# H-00488_-_Power.net
KiCad netlist of a schematic drawn in Altium Designer
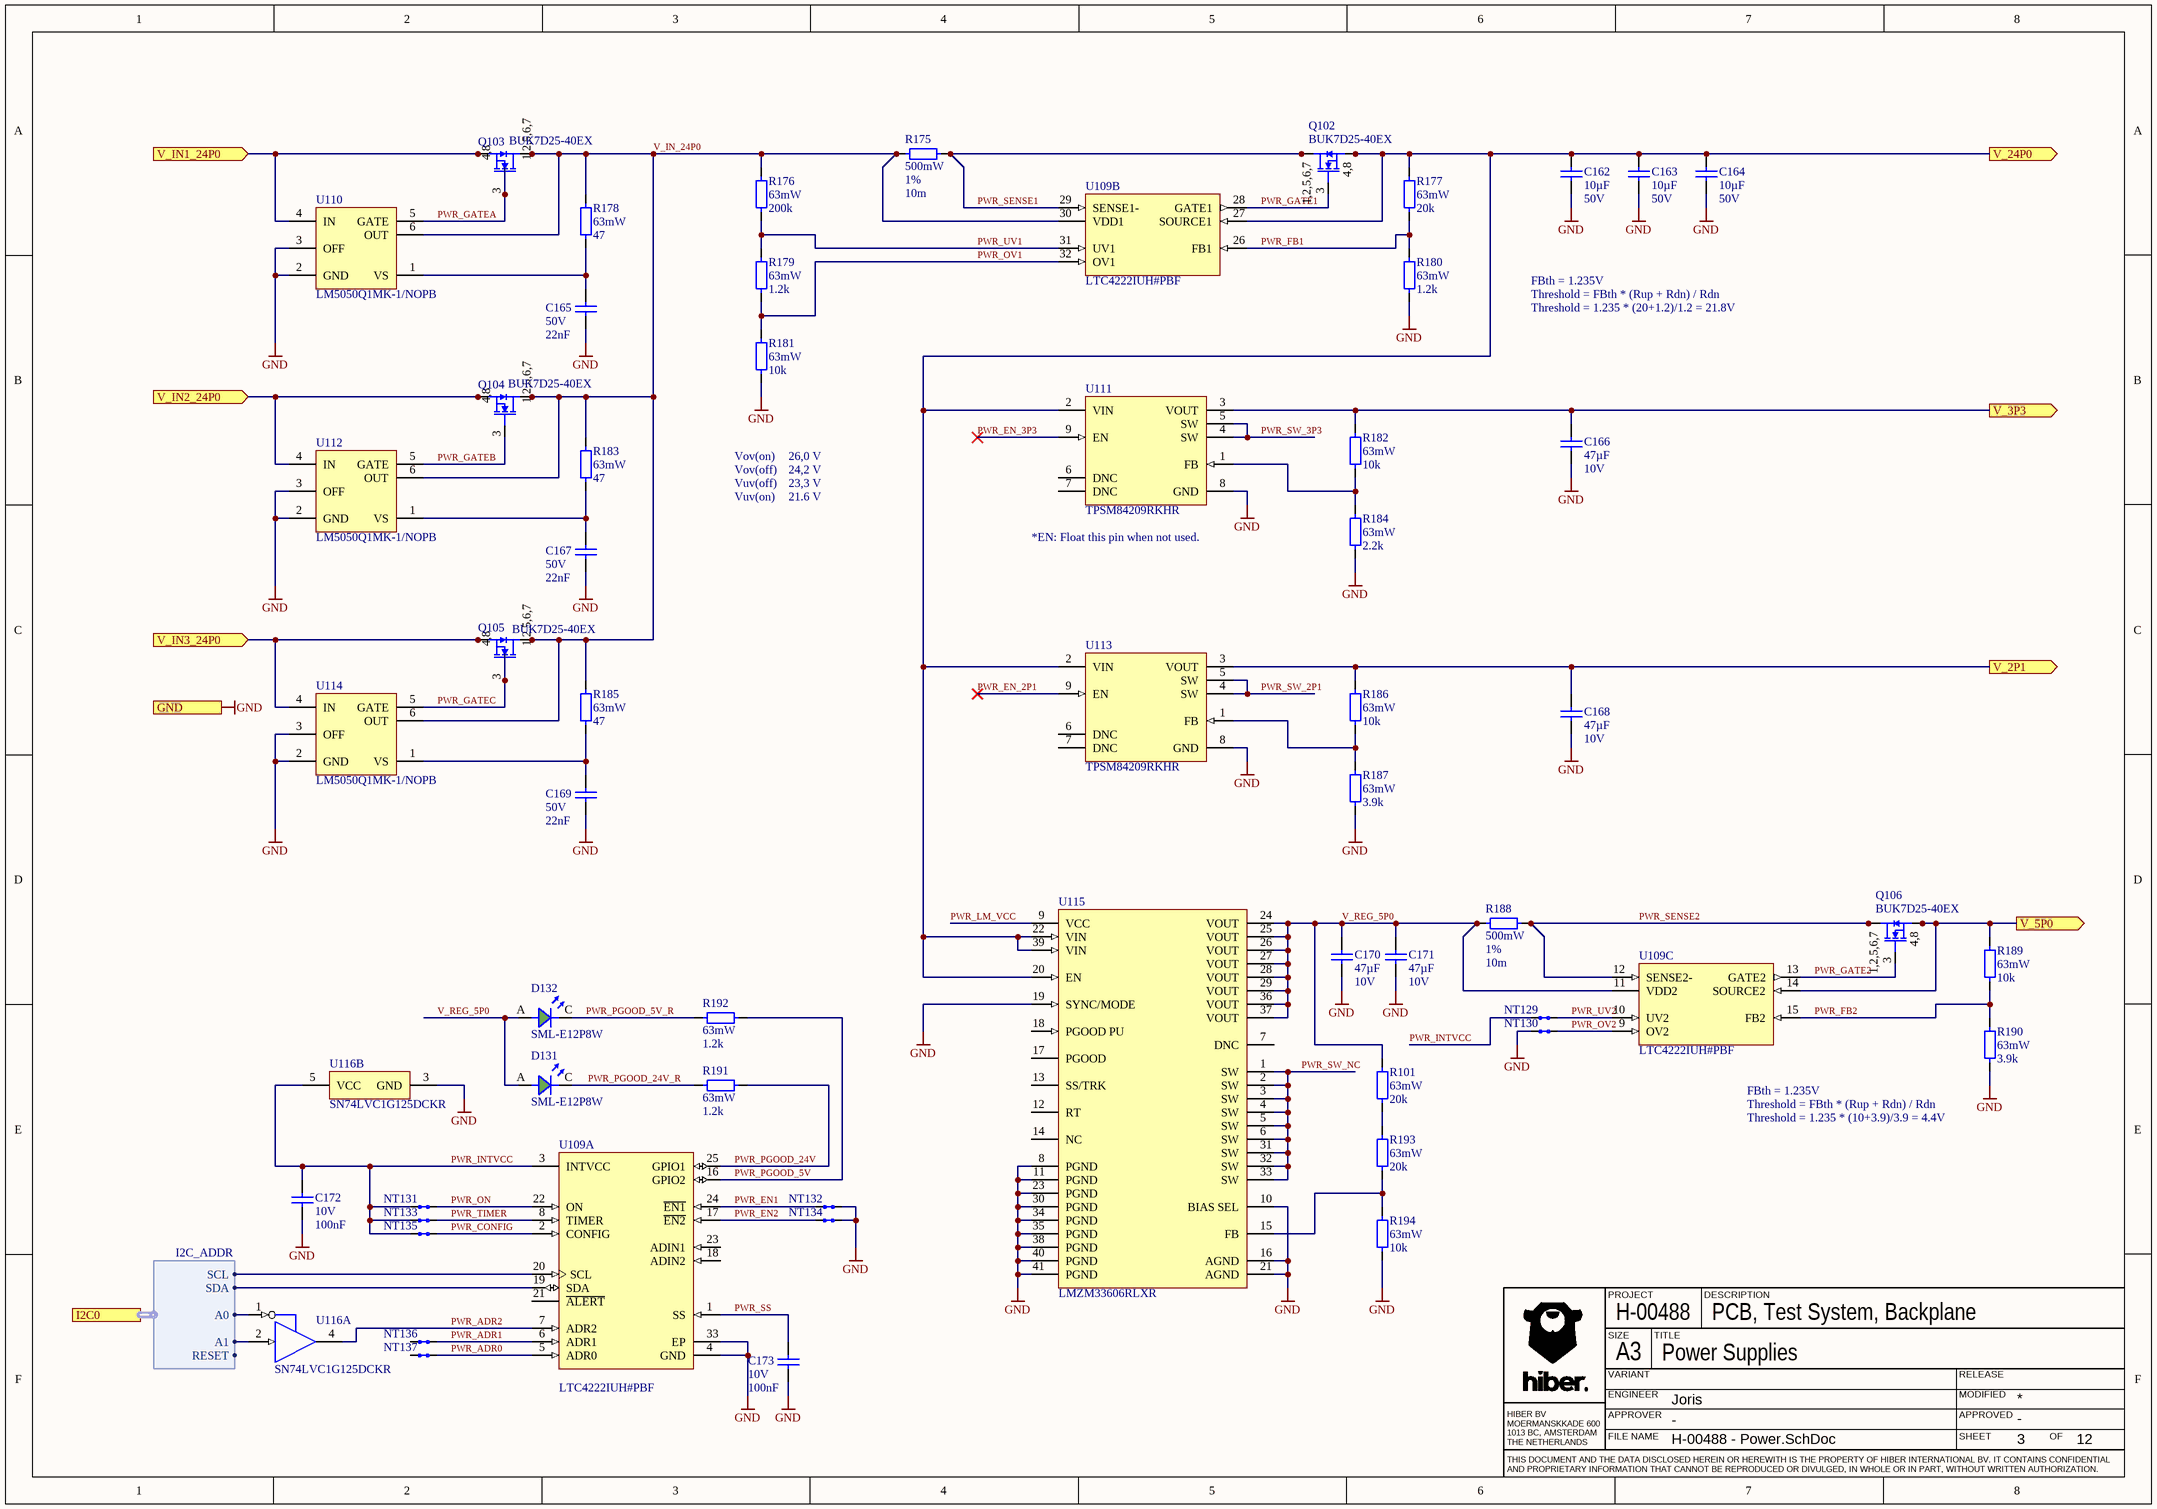
[diagram p0: H-00488 - Power.SchDoc]

(export (version "E")
  (design (tool "Eeschema 10.0.6"))
  (components
    (comp (ref "C162")
      (value "10µF")
      (footprint "CAPC320X250X245L50N")
      (description "CAP Standard 1210 (3225) 10,0uF 50V X7R (Standard)")
      (fields
        (field (name "TOLERANCE") "10%")
        (field (name "RATED VOLTAGE") "50V")
        (field (name "Comment") "C1210C106K5RACTU")
      )
      (libsource (lib "Hiber") (part "CAPACITOR"))
    )
    (comp (ref "C163")
      (value "10µF")
      (footprint "CAPC320X250X245L50N")
      (description "CAP Standard 1210 (3225) 10,0uF 50V X7R (Standard)")
      (fields
        (field (name "TOLERANCE") "10%")
        (field (name "RATED VOLTAGE") "50V")
        (field (name "Comment") "C1210C106K5RACTU")
      )
      (libsource (lib "Hiber") (part "CAPACITOR"))
    )
    (comp (ref "C164")
      (value "10µF")
      (footprint "CAPC320X250X245L50N")
      (description "CAP Standard 1210 (3225) 10,0uF 50V X7R (Standard)")
      (fields
        (field (name "TOLERANCE") "10%")
        (field (name "RATED VOLTAGE") "50V")
        (field (name "Comment") "C1210C106K5RACTU")
      )
      (libsource (lib "Hiber") (part "CAPACITOR"))
    )
    (comp (ref "C165")
      (value "22nF")
      (footprint "CAPC100X50X55L30N")
      (description "CAP Standard 0402 (1005) 22,0nF 50V X7R (Standard)")
      (fields
        (field (name "RATED VOLTAGE") "50V")
        (field (name "TOLERANCE") "10%")
        (field (name "Comment") "C0402C223K5RACTU")
      )
      (libsource (lib "Hiber") (part "CAPACITOR"))
    )
    (comp (ref "C166")
      (value "47µF")
      (footprint "CAPC320X250X170L50N")
      (description "CAP Standard 1210 (3225) 47,0uF 10V X7R (Standard)")
      (fields
        (field (name "RATED VOLTAGE") "10V")
        (field (name "TOLERANCE") "20%")
        (field (name "Comment") "C1210C476M8RACTU")
      )
      (libsource (lib "Hiber") (part "CAPACITOR"))
    )
    (comp (ref "C167")
      (value "22nF")
      (footprint "CAPC100X50X55L30N")
      (description "CAP Standard 0402 (1005) 22,0nF 50V X7R (Standard)")
      (fields
        (field (name "RATED VOLTAGE") "50V")
        (field (name "TOLERANCE") "10%")
        (field (name "Comment") "C0402C223K5RACTU")
      )
      (libsource (lib "Hiber") (part "CAPACITOR"))
    )
    (comp (ref "C168")
      (value "47µF")
      (footprint "CAPC320X250X170L50N")
      (description "CAP Standard 1210 (3225) 47,0uF 10V X7R (Standard)")
      (fields
        (field (name "RATED VOLTAGE") "10V")
        (field (name "TOLERANCE") "20%")
        (field (name "Comment") "C1210C476M8RACTU")
      )
      (libsource (lib "Hiber") (part "CAPACITOR"))
    )
    (comp (ref "C169")
      (value "22nF")
      (footprint "CAPC100X50X55L30N")
      (description "CAP Standard 0402 (1005) 22,0nF 50V X7R (Standard)")
      (fields
        (field (name "RATED VOLTAGE") "50V")
        (field (name "TOLERANCE") "10%")
        (field (name "Comment") "C0402C223K5RACTU")
      )
      (libsource (lib "Hiber") (part "CAPACITOR"))
    )
    (comp (ref "C170")
      (value "47µF")
      (footprint "CAPC320X250X170L50N")
      (description "CAP Standard 1210 (3225) 47,0uF 10V X7R (Standard)")
      (fields
        (field (name "RATED VOLTAGE") "10V")
        (field (name "TOLERANCE") "20%")
        (field (name "Comment") "C1210C476M8RACTU")
      )
      (libsource (lib "Hiber") (part "CAPACITOR"))
    )
    (comp (ref "C171")
      (value "47µF")
      (footprint "CAPC320X250X170L50N")
      (description "CAP Standard 1210 (3225) 47,0uF 10V X7R (Standard)")
      (fields
        (field (name "RATED VOLTAGE") "10V")
        (field (name "TOLERANCE") "20%")
        (field (name "Comment") "C1210C476M8RACTU")
      )
      (libsource (lib "Hiber") (part "CAPACITOR"))
    )
    (comp (ref "C172")
      (value "100nF")
      (footprint "CAPC100X50X55L30N")
      (description "CAP Standard 0402 (1005) 100,0nF 10V X7R (Standard)")
      (fields
        (field (name "RATED VOLTAGE") "10V")
        (field (name "TOLERANCE") "10%")
        (field (name "Comment") "C0402C104K8RACTU")
      )
      (libsource (lib "Hiber Vault") (part "CAPACITOR"))
    )
    (comp (ref "C173")
      (value "100nF")
      (footprint "CAPC100X50X55L30N")
      (description "CAP Standard 0402 (1005) 100,0nF 10V X7R (Standard)")
      (fields
        (field (name "RATED VOLTAGE") "10V")
        (field (name "TOLERANCE") "10%")
        (field (name "Comment") "C0402C104K8RACTU")
      )
      (libsource (lib "Hiber Vault") (part "CAPACITOR"))
    )
    (comp (ref "D131")
      (value "SML-E12P8W")
      (footprint "LEDC170X80X80L20_GREEN")
      (description "LED Green Diffused 0603 SMD")
      (libsource (lib "Hiber") (part "DIODE-LED-GREEN"))
    )
    (comp (ref "D132")
      (value "SML-E12P8W")
      (footprint "LEDC170X80X80L20_GREEN")
      (description "LED Green Diffused 0603 SMD")
      (libsource (lib "Hiber") (part "DIODE-LED-GREEN"))
    )
    (comp (ref "NT129")
      (value "NET-TIE")
      (footprint "NT200")
      (description "Net Tie, Inline")
      (libsource (lib "Hiber") (part "NET-TIE"))
    )
    (comp (ref "NT130")
      (value "NET-TIE")
      (footprint "NT200")
      (description "Net Tie, Inline")
      (libsource (lib "Hiber") (part "NET-TIE"))
    )
    (comp (ref "NT131")
      (value "NET-TIE")
      (footprint "NT200")
      (description "Net Tie, Inline")
      (libsource (lib "Hiber") (part "NET-TIE"))
    )
    (comp (ref "NT132")
      (value "NET-TIE")
      (footprint "NT200")
      (description "Net Tie, Inline")
      (libsource (lib "Hiber") (part "NET-TIE"))
    )
    (comp (ref "NT133")
      (value "NET-TIE")
      (footprint "NT200")
      (description "Net Tie, Inline")
      (libsource (lib "Hiber") (part "NET-TIE"))
    )
    (comp (ref "NT134")
      (value "NET-TIE")
      (footprint "NT200")
      (description "Net Tie, Inline")
      (libsource (lib "Hiber") (part "NET-TIE"))
    )
    (comp (ref "NT135")
      (value "NET-TIE")
      (footprint "NT200")
      (description "Net Tie, Inline")
      (libsource (lib "Hiber") (part "NET-TIE"))
    )
    (comp (ref "NT136")
      (value "NET-TIE")
      (footprint "NT200")
      (description "Net Tie, Inline")
      (libsource (lib "Hiber") (part "NET-TIE"))
    )
    (comp (ref "NT137")
      (value "NET-TIE")
      (footprint "NT200")
      (description "Net Tie, Inline")
      (libsource (lib "Hiber") (part "NET-TIE"))
    )
    (comp (ref "Q102")
      (value "BUK7D25-40EX")
      (footprint "NEXPERIA_SOT1220")
      (description "BUK7D25 Series 40V Surface-Mounted N-channel Trench MOSFET - SOT1118")
      (libsource (lib "Hiber") (part "MOSFET-N-8P-SOT1220"))
    )
    (comp (ref "Q103")
      (value "BUK7D25-40EX")
      (footprint "NEXPERIA_SOT1220")
      (description "BUK7D25 Series 40V Surface-Mounted N-channel Trench MOSFET - SOT1118")
      (libsource (lib "Hiber") (part "MOSFET-N-8P-SOT1220"))
    )
    (comp (ref "Q104")
      (value "BUK7D25-40EX")
      (footprint "NEXPERIA_SOT1220")
      (description "BUK7D25 Series 40V Surface-Mounted N-channel Trench MOSFET - SOT1118")
      (libsource (lib "Hiber") (part "MOSFET-N-8P-SOT1220"))
    )
    (comp (ref "Q105")
      (value "BUK7D25-40EX")
      (footprint "NEXPERIA_SOT1220")
      (description "BUK7D25 Series 40V Surface-Mounted N-channel Trench MOSFET - SOT1118")
      (libsource (lib "Hiber") (part "MOSFET-N-8P-SOT1220"))
    )
    (comp (ref "Q106")
      (value "BUK7D25-40EX")
      (footprint "NEXPERIA_SOT1220")
      (description "BUK7D25 Series 40V Surface-Mounted N-channel Trench MOSFET - SOT1118")
      (libsource (lib "Hiber") (part "MOSFET-N-8P-SOT1220"))
    )
    (comp (ref "R101")
      (value "20k")
      (footprint "RESC100X50X40L25N")
      (description "RES Standard Thick Film 0402 20K0 ±1% 0,063W")
      (fields
        (field (name "RATED POWER") "63mW")
        (field (name "TOLERANCE") "1%")
        (field (name "Comment") "CRCW040220K0FKED")
      )
      (libsource (lib "Hiber") (part "RESISTOR-2P"))
    )
    (comp (ref "R175")
      (value "10m")
      (footprint "RESC200X125X70L40M")
      (description "RES Power Metal Strip 0805 0R01 ±1% 0,5W")
      (fields
        (field (name "RATED POWER") "500mW")
        (field (name "TOLERANCE") "1%")
        (field (name "Comment") "WSLP0805R0100FEA")
      )
      (libsource (lib "Hiber Vault") (part "RESISTOR-2P"))
    )
    (comp (ref "R176")
      (value "200k")
      (footprint "RESC100X50X40L25N")
      (description "RES Standard Thick Film 0402 200K ±1% 0,063W")
      (fields
        (field (name "RATED POWER") "63mW")
        (field (name "TOLERANCE") "1%")
        (field (name "Comment") "CRCW0402200KFKED")
      )
      (libsource (lib "Hiber") (part "RESISTOR-2P"))
    )
    (comp (ref "R177")
      (value "20k")
      (footprint "RESC100X50X40L25N")
      (description "RES Standard Thick Film 0402 20K0 ±1% 0,063W")
      (fields
        (field (name "RATED POWER") "63mW")
        (field (name "TOLERANCE") "1%")
        (field (name "Comment") "CRCW040220K0FKED")
      )
      (libsource (lib "Hiber") (part "RESISTOR-2P"))
    )
    (comp (ref "R178")
      (value "47")
      (footprint "RESC100X50X40L25N")
      (description "RES Standard Thick Film 0402 47R0 ±1% 0,063W")
      (fields
        (field (name "RATED POWER") "63mW")
        (field (name "TOLERANCE") "1%")
        (field (name "Comment") "CRCW040247R0FKED")
      )
      (libsource (lib "Hiber") (part "RESISTOR-2P"))
    )
    (comp (ref "R179")
      (value "1.2k")
      (footprint "RESC100X50X40L25N")
      (description "RES Standard Thick Film 0402 1K20 ±1% 0,063W")
      (fields
        (field (name "RATED POWER") "63mW")
        (field (name "TOLERANCE") "1%")
        (field (name "Comment") "CRCW04021K20FKED")
      )
      (libsource (lib "Hiber") (part "RESISTOR-2P"))
    )
    (comp (ref "R180")
      (value "1.2k")
      (footprint "RESC100X50X40L25N")
      (description "RES Standard Thick Film 0402 1K20 ±1% 0,063W")
      (fields
        (field (name "RATED POWER") "63mW")
        (field (name "TOLERANCE") "1%")
        (field (name "Comment") "CRCW04021K20FKED")
      )
      (libsource (lib "Hiber") (part "RESISTOR-2P"))
    )
    (comp (ref "R181")
      (value "10k")
      (footprint "RESC100X50X40L25N")
      (description "RES Standard Thick Film 0402 10K0 ±1% 0,063W")
      (fields
        (field (name "RATED POWER") "63mW")
        (field (name "TOLERANCE") "1%")
        (field (name "Comment") "CRCW040210K0FKED")
      )
      (libsource (lib "Hiber") (part "RESISTOR-2P"))
    )
    (comp (ref "R182")
      (value "10k")
      (footprint "RESC100X50X40L25N")
      (description "RES Standard Thick Film 0402 10K0 ±1% 0,063W")
      (fields
        (field (name "RATED POWER") "63mW")
        (field (name "TOLERANCE") "1%")
        (field (name "Comment") "CRCW040210K0FKED")
      )
      (libsource (lib "Hiber") (part "RESISTOR-2P"))
    )
    (comp (ref "R183")
      (value "47")
      (footprint "RESC100X50X40L25N")
      (description "RES Standard Thick Film 0402 47R0 ±1% 0,063W")
      (fields
        (field (name "RATED POWER") "63mW")
        (field (name "TOLERANCE") "1%")
        (field (name "Comment") "CRCW040247R0FKED")
      )
      (libsource (lib "Hiber") (part "RESISTOR-2P"))
    )
    (comp (ref "R184")
      (value "2.2k")
      (footprint "RESC100X50X40L25N")
      (description "RES Standard Thick Film 0402 2K20 ±1% 0,063W")
      (fields
        (field (name "RATED POWER") "63mW")
        (field (name "TOLERANCE") "1%")
        (field (name "Comment") "CRCW04022K20FKED")
      )
      (libsource (lib "Hiber") (part "RESISTOR-2P"))
    )
    (comp (ref "R185")
      (value "47")
      (footprint "RESC100X50X40L25N")
      (description "RES Standard Thick Film 0402 47R0 ±1% 0,063W")
      (fields
        (field (name "RATED POWER") "63mW")
        (field (name "TOLERANCE") "1%")
        (field (name "Comment") "CRCW040247R0FKED")
      )
      (libsource (lib "Hiber") (part "RESISTOR-2P"))
    )
    (comp (ref "R186")
      (value "10k")
      (footprint "RESC100X50X40L25N")
      (description "RES Standard Thick Film 0402 10K0 ±1% 0,063W")
      (fields
        (field (name "RATED POWER") "63mW")
        (field (name "TOLERANCE") "1%")
        (field (name "Comment") "CRCW040210K0FKED")
      )
      (libsource (lib "Hiber") (part "RESISTOR-2P"))
    )
    (comp (ref "R187")
      (value "3.9k")
      (footprint "RESC100X50X40L25N")
      (description "RES Standard Thick Film 0402 3K90 ±1% 0,063W")
      (fields
        (field (name "RATED POWER") "63mW")
        (field (name "TOLERANCE") "1%")
        (field (name "Comment") "CRCW04023K90FKED")
      )
      (libsource (lib "Hiber") (part "RESISTOR-2P"))
    )
    (comp (ref "R188")
      (value "10m")
      (footprint "RESC200X125X70L40M")
      (description "RES Power Metal Strip 0805 0R01 ±1% 0,5W")
      (fields
        (field (name "RATED POWER") "500mW")
        (field (name "TOLERANCE") "1%")
        (field (name "Comment") "WSLP0805R0100FEA")
      )
      (libsource (lib "Hiber Vault") (part "RESISTOR-2P"))
    )
    (comp (ref "R189")
      (value "10k")
      (footprint "RESC100X50X40L25N")
      (description "RES Standard Thick Film 0402 10K0 ±1% 0,063W")
      (fields
        (field (name "RATED POWER") "63mW")
        (field (name "TOLERANCE") "1%")
        (field (name "Comment") "CRCW040210K0FKED")
      )
      (libsource (lib "Hiber") (part "RESISTOR-2P"))
    )
    (comp (ref "R190")
      (value "3.9k")
      (footprint "RESC100X50X40L25N")
      (description "RES Standard Thick Film 0402 3K90 ±1% 0,063W")
      (fields
        (field (name "RATED POWER") "63mW")
        (field (name "TOLERANCE") "1%")
        (field (name "Comment") "CRCW04023K90FKED")
      )
      (libsource (lib "Hiber") (part "RESISTOR-2P"))
    )
    (comp (ref "R191")
      (value "1.2k")
      (footprint "RESC100X50X40L25N")
      (description "RES Standard Thick Film 0402 1K20 ±1% 0,063W")
      (fields
        (field (name "RATED POWER") "63mW")
        (field (name "TOLERANCE") "1%")
        (field (name "Comment") "CRCW04021K20FKED")
      )
      (libsource (lib "Hiber") (part "RESISTOR-2P"))
    )
    (comp (ref "R192")
      (value "1.2k")
      (footprint "RESC100X50X40L25N")
      (description "RES Standard Thick Film 0402 1K20 ±1% 0,063W")
      (fields
        (field (name "RATED POWER") "63mW")
        (field (name "TOLERANCE") "1%")
        (field (name "Comment") "CRCW04021K20FKED")
      )
      (libsource (lib "Hiber") (part "RESISTOR-2P"))
    )
    (comp (ref "R193")
      (value "20k")
      (footprint "RESC100X50X40L25N")
      (description "RES Standard Thick Film 0402 20K0 ±1% 0,063W")
      (fields
        (field (name "RATED POWER") "63mW")
        (field (name "TOLERANCE") "1%")
        (field (name "Comment") "CRCW040220K0FKED")
      )
      (libsource (lib "Hiber") (part "RESISTOR-2P"))
    )
    (comp (ref "R194")
      (value "10k")
      (footprint "RESC100X50X40L25N")
      (description "RES Standard Thick Film 0402 10K0 ±1% 0,063W")
      (fields
        (field (name "RATED POWER") "63mW")
        (field (name "TOLERANCE") "1%")
        (field (name "Comment") "CRCW040210K0FKED")
      )
      (libsource (lib "Hiber") (part "RESISTOR-2P"))
    )
    (comp (ref "U109")
      (value "LTC4222IUH#PBF")
      (footprint "QFN33P50_500X500X80L40X25T345")
      (description "Power Supply Support Circuit, Adjustable, 2 Channel, CMOS, PQCC32")
      (libsource (lib "Hiber") (part "LT-LTC4222-UH-32"))
    )
    (comp (ref "U110")
      (value "LM5050Q1MK-1/NOPB")
      (footprint "SOT23-6P95_280X110L45X40M")
      (description "Half Bridge Based MOSFET Driver, PDSO6")
      (libsource (lib "Hiber") (part "LM5050Q1MK-1_NOPB"))
    )
    (comp (ref "U111")
      (value "TPSM84209RKHR")
      (footprint "TI_RKH0009A")
      (description "Switching Regulator, 2.5A, 923kHz Switching Freq-Max, PQCC9")
      (libsource (lib "Hiber") (part "TPSM84209RKHR"))
    )
    (comp (ref "U112")
      (value "LM5050Q1MK-1/NOPB")
      (footprint "SOT23-6P95_280X110L45X40M")
      (description "Half Bridge Based MOSFET Driver, PDSO6")
      (libsource (lib "Hiber") (part "LM5050Q1MK-1_NOPB"))
    )
    (comp (ref "U113")
      (value "TPSM84209RKHR")
      (footprint "TI_RKH0009A")
      (description "Switching Regulator, 2.5A, 923kHz Switching Freq-Max, PQCC9")
      (libsource (lib "Hiber") (part "TPSM84209RKHR"))
    )
    (comp (ref "U114")
      (value "LM5050Q1MK-1/NOPB")
      (footprint "SOT23-6P95_280X110L45X40M")
      (description "Half Bridge Based MOSFET Driver, PDSO6")
      (libsource (lib "Hiber") (part "LM5050Q1MK-1_NOPB"))
    )
    (comp (ref "U115")
      (value "LMZM33606RLXR")
      (footprint "TI_RLX0041A")
      (description "Switching Regulator, 6A, 2200kHz Switching Freq-Max, PQMA41")
      (libsource (lib "Hiber") (part "LMZM33606"))
    )
    (comp (ref "U116")
      (value "SN74LVC1G125DCKR")
      (footprint "SOT23-5P65_210X110L36X22")
      (description "Bus Driver, LVC/LCX/Z Series, 1-Func, 1-Bit, True Output, CMOS, PDSO5")
      (libsource (lib "Hiber") (part "TI-SN74AXXXX1X125-5"))
    )
  )
  (nets
    (net (code "2") (name "/A0") (class "Default")
      (node (ref "U116") (pin "1") (pinfunction "~{OE}_1") (pintype "input"))
    )
    (net (code "3") (name "/A1") (class "Default")
      (node (ref "U116") (pin "2") (pinfunction "A_2") (pintype "input"))
    )
    (net (code "4") (name "/PWR_ADR0") (class "Default")
      (node (ref "NT137") (pin "2") (pinfunction "1_2") (pintype "passive"))
      (node (ref "U109") (pin "5") (pinfunction "ADR0_5") (pintype "input"))
    )
    (net (code "5") (name "/PWR_ADR1") (class "Default")
      (node (ref "NT136") (pin "2") (pinfunction "1_2") (pintype "passive"))
      (node (ref "U109") (pin "6") (pinfunction "ADR1_6") (pintype "input"))
    )
    (net (code "6") (name "/PWR_ADR2") (class "Default")
      (node (ref "U109") (pin "7") (pinfunction "ADR2_7") (pintype "input"))
      (node (ref "U116") (pin "4") (pinfunction "Y_4") (pintype "tri_state"))
    )
    (net (code "7") (name "/PWR_CONFIG") (class "Default")
      (node (ref "NT135") (pin "2") (pinfunction "1_2") (pintype "passive"))
      (node (ref "U109") (pin "2") (pinfunction "CONFIG_2") (pintype "input"))
    )
    (net (code "8") (name "/PWR_EN1") (class "Default")
      (node (ref "NT132") (pin "1") (pinfunction "1_1") (pintype "passive"))
      (node (ref "U109") (pin "24") (pinfunction "~{EN1}_24") (pintype "input"))
    )
    (net (code "9") (name "/PWR_EN2") (class "Default")
      (node (ref "NT134") (pin "1") (pinfunction "1_1") (pintype "passive"))
      (node (ref "U109") (pin "17") (pinfunction "~{EN2}_17") (pintype "input"))
    )
    (net (code "10") (name "/PWR_EN_2P1") (class "Default")
      (node (ref "U113") (pin "9") (pinfunction "EN_9") (pintype "input+no_connect"))
    )
    (net (code "11") (name "/PWR_EN_3P3") (class "Default")
      (node (ref "U111") (pin "9") (pinfunction "EN_9") (pintype "input+no_connect"))
    )
    (net (code "12") (name "/PWR_FB1") (class "Default")
      (node (ref "R177") (pin "2") (pinfunction "2_2") (pintype "passive"))
      (node (ref "R180") (pin "1") (pinfunction "1_1") (pintype "passive"))
      (node (ref "U109") (pin "26") (pinfunction "FB1_26") (pintype "input"))
    )
    (net (code "13") (name "/PWR_FB2") (class "Default")
      (node (ref "R189") (pin "2") (pinfunction "2_2") (pintype "passive"))
      (node (ref "R190") (pin "1") (pinfunction "1_1") (pintype "passive"))
      (node (ref "U109") (pin "15") (pinfunction "FB2_15") (pintype "input"))
    )
    (net (code "14") (name "/PWR_GATE1") (class "Default")
      (node (ref "Q102") (pin "3") (pinfunction "G_3") (pintype "passive"))
      (node (ref "U109") (pin "28") (pinfunction "GATE1_28") (pintype "output"))
    )
    (net (code "15") (name "/PWR_GATE2") (class "Default")
      (node (ref "Q106") (pin "3") (pinfunction "G_3") (pintype "passive"))
      (node (ref "U109") (pin "13") (pinfunction "GATE2_13") (pintype "output"))
    )
    (net (code "16") (name "/PWR_GATEA") (class "Default")
      (node (ref "Q103") (pin "3") (pinfunction "G_3") (pintype "passive"))
      (node (ref "U110") (pin "5") (pinfunction "GATE_5") (pintype "passive"))
    )
    (net (code "17") (name "/PWR_GATEB") (class "Default")
      (node (ref "Q104") (pin "3") (pinfunction "G_3") (pintype "passive"))
      (node (ref "U112") (pin "5") (pinfunction "GATE_5") (pintype "passive"))
    )
    (net (code "18") (name "/PWR_GATEC") (class "Default")
      (node (ref "Q105") (pin "3") (pinfunction "G_3") (pintype "passive"))
      (node (ref "U114") (pin "5") (pinfunction "GATE_5") (pintype "passive"))
    )
    (net (code "19") (name "/PWR_INTVCC") (class "Default")
      (node (ref "C172") (pin "1") (pinfunction "1_1") (pintype "passive"))
      (node (ref "NT129") (pin "1") (pinfunction "1_1") (pintype "passive"))
      (node (ref "NT131") (pin "1") (pinfunction "1_1") (pintype "passive"))
      (node (ref "NT133") (pin "1") (pinfunction "1_1") (pintype "passive"))
      (node (ref "NT135") (pin "1") (pinfunction "1_1") (pintype "passive"))
      (node (ref "U109") (pin "3") (pinfunction "INTVCC_3") (pintype "power_in"))
      (node (ref "U116") (pin "5") (pinfunction "VCC_5") (pintype "power_in"))
    )
    (net (code "20") (name "/PWR_LM_VCC") (class "Default")
      (node (ref "U115") (pin "9") (pinfunction "VCC_9") (pintype "power_in"))
    )
    (net (code "21") (name "/PWR_ON") (class "Default")
      (node (ref "NT131") (pin "2") (pinfunction "1_2") (pintype "passive"))
      (node (ref "U109") (pin "22") (pinfunction "ON_22") (pintype "input"))
    )
    (net (code "22") (name "/PWR_OV1") (class "Default")
      (node (ref "R179") (pin "2") (pinfunction "2_2") (pintype "passive"))
      (node (ref "R181") (pin "1") (pinfunction "1_1") (pintype "passive"))
      (node (ref "U109") (pin "32") (pinfunction "OV1_32") (pintype "input"))
    )
    (net (code "23") (name "/PWR_OV2") (class "Default")
      (node (ref "NT130") (pin "2") (pinfunction "1_2") (pintype "passive"))
      (node (ref "U109") (pin "9") (pinfunction "OV2_9") (pintype "input"))
    )
    (net (code "24") (name "/PWR_PGOOD_5V") (class "Default")
      (node (ref "R192") (pin "2") (pinfunction "2_2") (pintype "passive"))
      (node (ref "U109") (pin "16") (pinfunction "GPIO2_16") (pintype "bidirectional"))
    )
    (net (code "25") (name "/PWR_PGOOD_5V_R") (class "Default")
      (node (ref "D132") (pin "C") (pinfunction "C_C") (pintype "passive"))
      (node (ref "R192") (pin "1") (pinfunction "1_1") (pintype "passive"))
    )
    (net (code "26") (name "/PWR_PGOOD_24V") (class "Default")
      (node (ref "R191") (pin "2") (pinfunction "2_2") (pintype "passive"))
      (node (ref "U109") (pin "25") (pinfunction "GPIO1_25") (pintype "bidirectional"))
    )
    (net (code "27") (name "/PWR_PGOOD_24V_R") (class "Default")
      (node (ref "D131") (pin "C") (pinfunction "C_C") (pintype "passive"))
      (node (ref "R191") (pin "1") (pinfunction "1_1") (pintype "passive"))
    )
    (net (code "28") (name "/PWR_SENSE1") (class "Default")
      (node (ref "Q102") (pin "1") (pinfunction "D_1") (pintype "passive"))
      (node (ref "Q102") (pin "2") (pinfunction "D_2") (pintype "passive"))
      (node (ref "Q102") (pin "5") (pinfunction "D_5") (pintype "passive"))
      (node (ref "Q102") (pin "6") (pinfunction "D_6") (pintype "passive"))
      (node (ref "Q102") (pin "7") (pinfunction "D_7") (pintype "passive"))
      (node (ref "R175") (pin "1") (pinfunction "1_1") (pintype "passive"))
      (node (ref "U109") (pin "29") (pinfunction "SENSE1-_29") (pintype "input"))
    )
    (net (code "29") (name "/PWR_SENSE2") (class "Default")
      (node (ref "Q106") (pin "1") (pinfunction "D_1") (pintype "passive"))
      (node (ref "Q106") (pin "2") (pinfunction "D_2") (pintype "passive"))
      (node (ref "Q106") (pin "5") (pinfunction "D_5") (pintype "passive"))
      (node (ref "Q106") (pin "6") (pinfunction "D_6") (pintype "passive"))
      (node (ref "Q106") (pin "7") (pinfunction "D_7") (pintype "passive"))
      (node (ref "R188") (pin "1") (pinfunction "1_1") (pintype "passive"))
      (node (ref "U109") (pin "12") (pinfunction "SENSE2-_12") (pintype "input"))
    )
    (net (code "30") (name "/PWR_SS") (class "Default")
      (node (ref "C173") (pin "1") (pinfunction "1_1") (pintype "passive"))
      (node (ref "U109") (pin "1") (pinfunction "SS_1") (pintype "input"))
    )
    (net (code "31") (name "/PWR_SW_2P1") (class "Default")
      (node (ref "U113") (pin "4") (pinfunction "SW_4") (pintype "power_in"))
      (node (ref "U113") (pin "5") (pinfunction "SW_5") (pintype "power_in"))
    )
    (net (code "32") (name "/PWR_SW_3P3") (class "Default")
      (node (ref "U111") (pin "4") (pinfunction "SW_4") (pintype "power_in"))
      (node (ref "U111") (pin "5") (pinfunction "SW_5") (pintype "power_in"))
    )
    (net (code "33") (name "/PWR_SW_NC") (class "Default")
      (node (ref "U115") (pin "1") (pinfunction "SW_1") (pintype "passive"))
      (node (ref "U115") (pin "2") (pinfunction "SW_2") (pintype "passive"))
      (node (ref "U115") (pin "3") (pinfunction "SW_3") (pintype "passive"))
      (node (ref "U115") (pin "31") (pinfunction "SW_31") (pintype "passive"))
      (node (ref "U115") (pin "32") (pinfunction "SW_32") (pintype "passive"))
      (node (ref "U115") (pin "33") (pinfunction "SW_33") (pintype "passive"))
      (node (ref "U115") (pin "4") (pinfunction "SW_4") (pintype "passive"))
      (node (ref "U115") (pin "5") (pinfunction "SW_5") (pintype "passive"))
      (node (ref "U115") (pin "6") (pinfunction "SW_6") (pintype "passive"))
    )
    (net (code "34") (name "/PWR_TIMER") (class "Default")
      (node (ref "NT133") (pin "2") (pinfunction "1_2") (pintype "passive"))
      (node (ref "U109") (pin "8") (pinfunction "TIMER_8") (pintype "input"))
    )
    (net (code "35") (name "/PWR_UV1") (class "Default")
      (node (ref "R176") (pin "2") (pinfunction "2_2") (pintype "passive"))
      (node (ref "R179") (pin "1") (pinfunction "1_1") (pintype "passive"))
      (node (ref "U109") (pin "31") (pinfunction "UV1_31") (pintype "input"))
    )
    (net (code "36") (name "/PWR_UV2") (class "Default")
      (node (ref "NT129") (pin "2") (pinfunction "1_2") (pintype "passive"))
      (node (ref "U109") (pin "10") (pinfunction "UV2_10") (pintype "input"))
    )
    (net (code "37") (name "/SCL") (class "Default")
      (node (ref "U109") (pin "20") (pinfunction "SCL_20") (pintype "input"))
    )
    (net (code "38") (name "/SDA") (class "Default")
      (node (ref "U109") (pin "19") (pinfunction "SDA_19") (pintype "bidirectional"))
    )
    (net (code "39") (name "/V_2P1") (class "Default")
      (node (ref "C168") (pin "1") (pinfunction "1_1") (pintype "passive"))
      (node (ref "R186") (pin "1") (pinfunction "1_1") (pintype "passive"))
      (node (ref "U113") (pin "3") (pinfunction "VOUT_3") (pintype "power_in"))
    )
    (net (code "40") (name "/V_3P3") (class "Default")
      (node (ref "C166") (pin "1") (pinfunction "1_1") (pintype "passive"))
      (node (ref "R182") (pin "1") (pinfunction "1_1") (pintype "passive"))
      (node (ref "U111") (pin "3") (pinfunction "VOUT_3") (pintype "power_in"))
    )
    (net (code "41") (name "/V_5P0") (class "Default")
      (node (ref "Q106") (pin "4") (pinfunction "S_4") (pintype "passive"))
      (node (ref "Q106") (pin "8") (pinfunction "S_8") (pintype "passive"))
      (node (ref "R189") (pin "1") (pinfunction "1_1") (pintype "passive"))
      (node (ref "U109") (pin "14") (pinfunction "SOURCE2_14") (pintype "input"))
    )
    (net (code "42") (name "/V_24P0") (class "Default")
      (node (ref "C162") (pin "2") (pinfunction "2_2") (pintype "passive"))
      (node (ref "C163") (pin "2") (pinfunction "2_2") (pintype "passive"))
      (node (ref "C164") (pin "2") (pinfunction "2_2") (pintype "passive"))
      (node (ref "Q102") (pin "4") (pinfunction "S_4") (pintype "passive"))
      (node (ref "Q102") (pin "8") (pinfunction "S_8") (pintype "passive"))
      (node (ref "R177") (pin "1") (pinfunction "1_1") (pintype "passive"))
      (node (ref "U109") (pin "27") (pinfunction "SOURCE1_27") (pintype "input"))
      (node (ref "U111") (pin "2") (pinfunction "VIN_2") (pintype "power_in"))
      (node (ref "U113") (pin "2") (pinfunction "VIN_2") (pintype "power_in"))
      (node (ref "U115") (pin "20") (pinfunction "EN_20") (pintype "input"))
      (node (ref "U115") (pin "22") (pinfunction "VIN_22") (pintype "input"))
      (node (ref "U115") (pin "39") (pinfunction "VIN_39") (pintype "input"))
    )
    (net (code "43") (name "/V_IN1_24P0") (class "Default")
      (node (ref "Q103") (pin "4") (pinfunction "S_4") (pintype "passive"))
      (node (ref "Q103") (pin "8") (pinfunction "S_8") (pintype "passive"))
      (node (ref "U110") (pin "4") (pinfunction "IN_4") (pintype "passive"))
    )
    (net (code "44") (name "/V_IN2_24P0") (class "Default")
      (node (ref "Q104") (pin "4") (pinfunction "S_4") (pintype "passive"))
      (node (ref "Q104") (pin "8") (pinfunction "S_8") (pintype "passive"))
      (node (ref "U112") (pin "4") (pinfunction "IN_4") (pintype "passive"))
    )
    (net (code "45") (name "/V_IN3_24P0") (class "Default")
      (node (ref "Q105") (pin "4") (pinfunction "S_4") (pintype "passive"))
      (node (ref "Q105") (pin "8") (pinfunction "S_8") (pintype "passive"))
      (node (ref "U114") (pin "4") (pinfunction "IN_4") (pintype "passive"))
    )
    (net (code "46") (name "/V_IN_24P0") (class "Default")
      (node (ref "Q103") (pin "1") (pinfunction "D_1") (pintype "passive"))
      (node (ref "Q103") (pin "2") (pinfunction "D_2") (pintype "passive"))
      (node (ref "Q103") (pin "5") (pinfunction "D_5") (pintype "passive"))
      (node (ref "Q103") (pin "6") (pinfunction "D_6") (pintype "passive"))
      (node (ref "Q103") (pin "7") (pinfunction "D_7") (pintype "passive"))
      (node (ref "Q104") (pin "1") (pinfunction "D_1") (pintype "passive"))
      (node (ref "Q104") (pin "2") (pinfunction "D_2") (pintype "passive"))
      (node (ref "Q104") (pin "5") (pinfunction "D_5") (pintype "passive"))
      (node (ref "Q104") (pin "6") (pinfunction "D_6") (pintype "passive"))
      (node (ref "Q104") (pin "7") (pinfunction "D_7") (pintype "passive"))
      (node (ref "Q105") (pin "1") (pinfunction "D_1") (pintype "passive"))
      (node (ref "Q105") (pin "2") (pinfunction "D_2") (pintype "passive"))
      (node (ref "Q105") (pin "5") (pinfunction "D_5") (pintype "passive"))
      (node (ref "Q105") (pin "6") (pinfunction "D_6") (pintype "passive"))
      (node (ref "Q105") (pin "7") (pinfunction "D_7") (pintype "passive"))
      (node (ref "R175") (pin "2") (pinfunction "2_2") (pintype "passive"))
      (node (ref "R176") (pin "1") (pinfunction "1_1") (pintype "passive"))
      (node (ref "R178") (pin "1") (pinfunction "1_1") (pintype "passive"))
      (node (ref "R183") (pin "1") (pinfunction "1_1") (pintype "passive"))
      (node (ref "R185") (pin "1") (pinfunction "1_1") (pintype "passive"))
      (node (ref "U109") (pin "30") (pinfunction "VDD1_30") (pintype "power_in"))
      (node (ref "U110") (pin "6") (pinfunction "OUT_6") (pintype "passive"))
      (node (ref "U112") (pin "6") (pinfunction "OUT_6") (pintype "passive"))
      (node (ref "U114") (pin "6") (pinfunction "OUT_6") (pintype "passive"))
    )
    (net (code "47") (name "/V_REG_5P0") (class "Default")
      (node (ref "C170") (pin "1") (pinfunction "1_1") (pintype "passive"))
      (node (ref "C171") (pin "1") (pinfunction "1_1") (pintype "passive"))
      (node (ref "D131") (pin "A") (pinfunction "A_A") (pintype "passive"))
      (node (ref "D132") (pin "A") (pinfunction "A_A") (pintype "passive"))
      (node (ref "R101") (pin "1") (pinfunction "1_1") (pintype "passive"))
      (node (ref "R188") (pin "2") (pinfunction "2_2") (pintype "passive"))
      (node (ref "U109") (pin "11") (pinfunction "VDD2_11") (pintype "power_in"))
      (node (ref "U115") (pin "24") (pinfunction "VOUT_24") (pintype "power_in"))
      (node (ref "U115") (pin "25") (pinfunction "VOUT_25") (pintype "power_in"))
      (node (ref "U115") (pin "26") (pinfunction "VOUT_26") (pintype "power_in"))
      (node (ref "U115") (pin "27") (pinfunction "VOUT_27") (pintype "power_in"))
      (node (ref "U115") (pin "28") (pinfunction "VOUT_28") (pintype "power_in"))
      (node (ref "U115") (pin "29") (pinfunction "VOUT_29") (pintype "power_in"))
      (node (ref "U115") (pin "36") (pinfunction "VOUT_36") (pintype "power_in"))
      (node (ref "U115") (pin "37") (pinfunction "VOUT_37") (pintype "power_in"))
    )
    (net (code "49") (name "GND") (class "Default")
      (node (ref "C162") (pin "1") (pinfunction "1_1") (pintype "passive"))
      (node (ref "C163") (pin "1") (pinfunction "1_1") (pintype "passive"))
      (node (ref "C164") (pin "1") (pinfunction "1_1") (pintype "passive"))
      (node (ref "C165") (pin "2") (pinfunction "2_2") (pintype "passive"))
      (node (ref "C166") (pin "2") (pinfunction "2_2") (pintype "passive"))
      (node (ref "C167") (pin "2") (pinfunction "2_2") (pintype "passive"))
      (node (ref "C168") (pin "2") (pinfunction "2_2") (pintype "passive"))
      (node (ref "C169") (pin "2") (pinfunction "2_2") (pintype "passive"))
      (node (ref "C170") (pin "2") (pinfunction "2_2") (pintype "passive"))
      (node (ref "C171") (pin "2") (pinfunction "2_2") (pintype "passive"))
      (node (ref "C172") (pin "2") (pinfunction "2_2") (pintype "passive"))
      (node (ref "C173") (pin "2") (pinfunction "2_2") (pintype "passive"))
      (node (ref "NT130") (pin "1") (pinfunction "1_1") (pintype "passive"))
      (node (ref "NT132") (pin "2") (pinfunction "1_2") (pintype "passive"))
      (node (ref "NT134") (pin "2") (pinfunction "1_2") (pintype "passive"))
      (node (ref "R180") (pin "2") (pinfunction "2_2") (pintype "passive"))
      (node (ref "R181") (pin "2") (pinfunction "2_2") (pintype "passive"))
      (node (ref "R184") (pin "2") (pinfunction "2_2") (pintype "passive"))
      (node (ref "R187") (pin "2") (pinfunction "2_2") (pintype "passive"))
      (node (ref "R190") (pin "2") (pinfunction "2_2") (pintype "passive"))
      (node (ref "R194") (pin "2") (pinfunction "2_2") (pintype "passive"))
      (node (ref "U109") (pin "33") (pinfunction "EP_33") (pintype "power_in"))
      (node (ref "U109") (pin "4") (pinfunction "GND_4") (pintype "power_in"))
      (node (ref "U110") (pin "2") (pinfunction "GND_2") (pintype "passive"))
      (node (ref "U110") (pin "3") (pinfunction "OFF_3") (pintype "passive"))
      (node (ref "U111") (pin "8") (pinfunction "GND_8") (pintype "power_in"))
      (node (ref "U112") (pin "2") (pinfunction "GND_2") (pintype "passive"))
      (node (ref "U112") (pin "3") (pinfunction "OFF_3") (pintype "passive"))
      (node (ref "U113") (pin "8") (pinfunction "GND_8") (pintype "power_in"))
      (node (ref "U114") (pin "2") (pinfunction "GND_2") (pintype "passive"))
      (node (ref "U114") (pin "3") (pinfunction "OFF_3") (pintype "passive"))
      (node (ref "U115") (pin "10") (pinfunction "BIAS_SEL_10") (pintype "passive"))
      (node (ref "U115") (pin "11") (pinfunction "PGND_11") (pintype "power_in"))
      (node (ref "U115") (pin "16") (pinfunction "AGND_16") (pintype "power_in"))
      (node (ref "U115") (pin "19") (pinfunction "SYNC/MODE_19") (pintype "input"))
      (node (ref "U115") (pin "21") (pinfunction "AGND_21") (pintype "power_in"))
      (node (ref "U115") (pin "23") (pinfunction "PGND_23") (pintype "power_in"))
      (node (ref "U115") (pin "30") (pinfunction "PGND_30") (pintype "power_in"))
      (node (ref "U115") (pin "34") (pinfunction "PGND_34") (pintype "power_in"))
      (node (ref "U115") (pin "35") (pinfunction "PGND_35") (pintype "power_in"))
      (node (ref "U115") (pin "38") (pinfunction "PGND_38") (pintype "power_in"))
      (node (ref "U115") (pin "40") (pinfunction "PGND_40") (pintype "power_in"))
      (node (ref "U115") (pin "41") (pinfunction "PGND_41") (pintype "power_in"))
      (node (ref "U115") (pin "8") (pinfunction "PGND_8") (pintype "power_in"))
      (node (ref "U116") (pin "3") (pinfunction "GND_3") (pintype "power_in"))
    )
    (net (code "50") (name "Net-(R101-Pad2)") (class "Default")
      (node (ref "R101") (pin "2") (pinfunction "2_2") (pintype "passive"))
      (node (ref "R193") (pin "1") (pinfunction "1_1") (pintype "passive"))
    )
    (net (code "51") (name "Net-(U110-VS)") (class "Default")
      (node (ref "C165") (pin "1") (pinfunction "1_1") (pintype "passive"))
      (node (ref "R178") (pin "2") (pinfunction "2_2") (pintype "passive"))
      (node (ref "U110") (pin "1") (pinfunction "VS_1") (pintype "passive"))
    )
    (net (code "52") (name "Net-(U111-FB)") (class "Default")
      (node (ref "R182") (pin "2") (pinfunction "2_2") (pintype "passive"))
      (node (ref "R184") (pin "1") (pinfunction "1_1") (pintype "passive"))
      (node (ref "U111") (pin "1") (pinfunction "FB_1") (pintype "input"))
    )
    (net (code "53") (name "Net-(U112-VS)") (class "Default")
      (node (ref "C167") (pin "1") (pinfunction "1_1") (pintype "passive"))
      (node (ref "R183") (pin "2") (pinfunction "2_2") (pintype "passive"))
      (node (ref "U112") (pin "1") (pinfunction "VS_1") (pintype "passive"))
    )
    (net (code "54") (name "Net-(U113-FB)") (class "Default")
      (node (ref "R186") (pin "2") (pinfunction "2_2") (pintype "passive"))
      (node (ref "R187") (pin "1") (pinfunction "1_1") (pintype "passive"))
      (node (ref "U113") (pin "1") (pinfunction "FB_1") (pintype "input"))
    )
    (net (code "55") (name "Net-(U114-VS)") (class "Default")
      (node (ref "C169") (pin "1") (pinfunction "1_1") (pintype "passive"))
      (node (ref "R185") (pin "2") (pinfunction "2_2") (pintype "passive"))
      (node (ref "U114") (pin "1") (pinfunction "VS_1") (pintype "passive"))
    )
    (net (code "56") (name "Net-(U115-FB)") (class "Default")
      (node (ref "R193") (pin "2") (pinfunction "2_2") (pintype "passive"))
      (node (ref "R194") (pin "1") (pinfunction "1_1") (pintype "passive"))
      (node (ref "U115") (pin "15") (pinfunction "FB_15") (pintype "passive"))
    )
    (net (code "57") (name "unconnected-(NT136-Pad1)") (class "Default")
      (node (ref "NT136") (pin "1") (pinfunction "1_1") (pintype "passive"))
    )
    (net (code "58") (name "unconnected-(NT137-Pad1)") (class "Default")
      (node (ref "NT137") (pin "1") (pinfunction "1_1") (pintype "passive"))
    )
    (net (code "59") (name "unconnected-(U109A-ADIN1-Pad23)") (class "Default")
      (node (ref "U109") (pin "23") (pinfunction "ADIN1_23") (pintype "input"))
    )
    (net (code "60") (name "unconnected-(U109A-ADIN2-Pad18)") (class "Default")
      (node (ref "U109") (pin "18") (pinfunction "ADIN2_18") (pintype "input"))
    )
    (net (code "61") (name "unconnected-(U109A-~{ALERT}-Pad21)") (class "Default")
      (node (ref "U109") (pin "21") (pinfunction "~{ALERT}_21") (pintype "open_collector"))
    )
    (net (code "62") (name "unconnected-(U111-DNC-Pad6)") (class "Default")
      (node (ref "U111") (pin "6") (pinfunction "DNC_6") (pintype "passive"))
    )
    (net (code "63") (name "unconnected-(U111-DNC-Pad7)") (class "Default")
      (node (ref "U111") (pin "7") (pinfunction "DNC_7") (pintype "passive"))
    )
    (net (code "64") (name "unconnected-(U113-DNC-Pad6)") (class "Default")
      (node (ref "U113") (pin "6") (pinfunction "DNC_6") (pintype "passive"))
    )
    (net (code "65") (name "unconnected-(U113-DNC-Pad7)") (class "Default")
      (node (ref "U113") (pin "7") (pinfunction "DNC_7") (pintype "passive"))
    )
    (net (code "66") (name "unconnected-(U115-DNC-Pad7)") (class "Default")
      (node (ref "U115") (pin "7") (pinfunction "DNC_7") (pintype "passive"))
    )
    (net (code "67") (name "unconnected-(U115-NC-Pad14)") (class "Default")
      (node (ref "U115") (pin "14") (pinfunction "NC_14") (pintype "passive"))
    )
    (net (code "68") (name "unconnected-(U115-PGOOD-Pad17)") (class "Default")
      (node (ref "U115") (pin "17") (pinfunction "PGOOD_17") (pintype "open_collector"))
    )
    (net (code "69") (name "unconnected-(U115-PGOOD_PU-Pad18)") (class "Default")
      (node (ref "U115") (pin "18") (pinfunction "PGOOD_PU_18") (pintype "input"))
    )
    (net (code "70") (name "unconnected-(U115-RT-Pad12)") (class "Default")
      (node (ref "U115") (pin "12") (pinfunction "RT_12") (pintype "passive"))
    )
    (net (code "71") (name "unconnected-(U115-SS{slash}TRK-Pad13)") (class "Default")
      (node (ref "U115") (pin "13") (pinfunction "SS/TRK_13") (pintype "passive"))
    )
  )
)
